# SDCard.net
KiCad netlist of a schematic drawn in Altium Designer
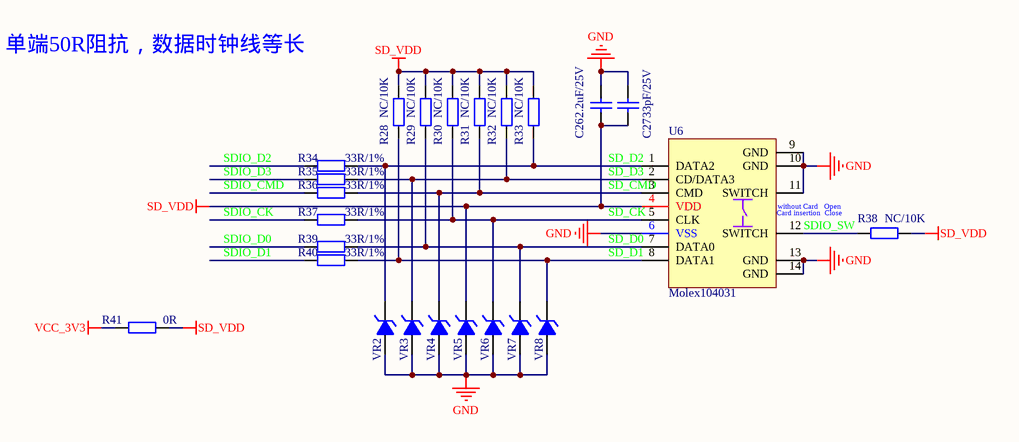
[diagram p0: SDCard.SchDoc]

(export (version "E")
  (design (tool "Eeschema 10.0.6"))
  (components
    (comp (ref "C26")
      (value "2.2uF/25V")
      (footprint "C0402_L")
      (description "贴片电容")
      (libsource (lib "0.1 - 电阻-电容-电感-晶振-晶体-磁珠-电位器") (part "C"))
    )
    (comp (ref "C27")
      (value "33pF/25V")
      (footprint "C0402_L")
      (description "贴片电容")
      (libsource (lib "0.1 - 电阻-电容-电感-晶振-晶体-磁珠-电位器") (part "C"))
    )
    (comp (ref "R28")
      (value "NC/10K")
      (footprint "R0402_L")
      (description "贴片电阻")
      (libsource (lib "0.1 - 电阻-电容-电感-晶振-晶体-磁珠-电位器") (part "R"))
    )
    (comp (ref "R29")
      (value "NC/10K")
      (footprint "R0402_L")
      (description "贴片电阻")
      (libsource (lib "0.1 - 电阻-电容-电感-晶振-晶体-磁珠-电位器") (part "R"))
    )
    (comp (ref "R30")
      (value "NC/10K")
      (footprint "R0402_L")
      (description "贴片电阻")
      (libsource (lib "0.1 - 电阻-电容-电感-晶振-晶体-磁珠-电位器") (part "R"))
    )
    (comp (ref "R31")
      (value "NC/10K")
      (footprint "R0402_L")
      (description "贴片电阻")
      (libsource (lib "0.1 - 电阻-电容-电感-晶振-晶体-磁珠-电位器") (part "R"))
    )
    (comp (ref "R32")
      (value "NC/10K")
      (footprint "R0402_L")
      (description "贴片电阻")
      (libsource (lib "0.1 - 电阻-电容-电感-晶振-晶体-磁珠-电位器") (part "R"))
    )
    (comp (ref "R33")
      (value "NC/10K")
      (footprint "R0402_L")
      (description "贴片电阻")
      (libsource (lib "0.1 - 电阻-电容-电感-晶振-晶体-磁珠-电位器") (part "R"))
    )
    (comp (ref "R34")
      (value "33R/1%")
      (footprint "R0402_L")
      (description "贴片电阻")
      (libsource (lib "0.1 - 电阻-电容-电感-晶振-晶体-磁珠-电位器") (part "R"))
    )
    (comp (ref "R35")
      (value "33R/1%")
      (footprint "R0402_L")
      (description "贴片电阻")
      (libsource (lib "0.1 - 电阻-电容-电感-晶振-晶体-磁珠-电位器") (part "R"))
    )
    (comp (ref "R36")
      (value "33R/1%")
      (footprint "R0402_L")
      (description "贴片电阻")
      (libsource (lib "0.1 - 电阻-电容-电感-晶振-晶体-磁珠-电位器") (part "R"))
    )
    (comp (ref "R37")
      (value "33R/1%")
      (footprint "R0402_L")
      (description "贴片电阻")
      (libsource (lib "0.1 - 电阻-电容-电感-晶振-晶体-磁珠-电位器") (part "R"))
    )
    (comp (ref "R38")
      (value "NC/10K")
      (footprint "R0402_L")
      (description "贴片电阻")
      (libsource (lib "0.1 - 电阻-电容-电感-晶振-晶体-磁珠-电位器") (part "R"))
    )
    (comp (ref "R39")
      (value "33R/1%")
      (footprint "R0402_L")
      (description "贴片电阻")
      (libsource (lib "0.1 - 电阻-电容-电感-晶振-晶体-磁珠-电位器") (part "R"))
    )
    (comp (ref "R40")
      (value "33R/1%")
      (footprint "R0402_L")
      (description "贴片电阻")
      (libsource (lib "0.1 - 电阻-电容-电感-晶振-晶体-磁珠-电位器") (part "R"))
    )
    (comp (ref "R41")
      (value "0R")
      (footprint "R0402_L")
      (description "贴片电阻")
      (libsource (lib "0.1 - 电阻-电容-电感-晶振-晶体-磁珠-电位器") (part "R"))
    )
    (comp (ref "U6")
      (value "Molex104031")
      (footprint "插拔式MicroSD卡")
      (description "拔插式超薄TF卡座")
      (libsource (lib "USER_Lib") (part "Molex104031"))
    )
    (comp (ref "VR2")
      (value "ESD9D5U")
      (footprint "SOD-923")
      (description "瞬态电压抑制二极管")
      (libsource (lib "二极管") (part "Diode4"))
    )
    (comp (ref "VR3")
      (value "ESD9D5U")
      (footprint "SOD-923")
      (description "瞬态电压抑制二极管")
      (libsource (lib "二极管") (part "Diode4"))
    )
    (comp (ref "VR4")
      (value "ESD9D5U")
      (footprint "SOD-923")
      (description "瞬态电压抑制二极管")
      (libsource (lib "二极管") (part "Diode4"))
    )
    (comp (ref "VR5")
      (value "ESD9D5U")
      (footprint "SOD-923")
      (description "瞬态电压抑制二极管")
      (libsource (lib "二极管") (part "Diode4"))
    )
    (comp (ref "VR6")
      (value "ESD9D5U")
      (footprint "SOD-923")
      (description "瞬态电压抑制二极管")
      (libsource (lib "二极管") (part "Diode4"))
    )
    (comp (ref "VR7")
      (value "ESD9D5U")
      (footprint "SOD-923")
      (description "瞬态电压抑制二极管")
      (libsource (lib "二极管") (part "Diode4"))
    )
    (comp (ref "VR8")
      (value "ESD9D5U")
      (footprint "SOD-923")
      (description "瞬态电压抑制二极管")
      (libsource (lib "二极管") (part "Diode4"))
    )
  )
  (nets
    (net (code "1") (name "/SDIO_CK") (class "Default")
      (node (ref "R37") (pin "1") (pinfunction "1_1") (pintype "passive"))
    )
    (net (code "2") (name "/SDIO_CMD") (class "Default")
      (node (ref "R36") (pin "1") (pinfunction "1_1") (pintype "passive"))
    )
    (net (code "3") (name "/SDIO_D0") (class "Default")
      (node (ref "R39") (pin "1") (pinfunction "1_1") (pintype "passive"))
    )
    (net (code "4") (name "/SDIO_D1") (class "Default")
      (node (ref "R40") (pin "1") (pinfunction "1_1") (pintype "passive"))
    )
    (net (code "5") (name "/SDIO_D2") (class "Default")
      (node (ref "R34") (pin "1") (pinfunction "1_1") (pintype "passive"))
    )
    (net (code "6") (name "/SDIO_D3") (class "Default")
      (node (ref "R35") (pin "1") (pinfunction "1_1") (pintype "passive"))
    )
    (net (code "7") (name "/SDIO_SW") (class "Default")
      (node (ref "R38") (pin "2") (pinfunction "2_2") (pintype "passive"))
      (node (ref "U6") (pin "12") (pinfunction "SWITCH_12") (pintype "passive"))
    )
    (net (code "8") (name "/SD_CK") (class "Default")
      (node (ref "R30") (pin "1") (pinfunction "1_1") (pintype "passive"))
      (node (ref "R37") (pin "2") (pinfunction "2_2") (pintype "passive"))
      (node (ref "U6") (pin "5") (pinfunction "CLK_5") (pintype "passive"))
      (node (ref "VR6") (pin "1") (pinfunction "K_1") (pintype "passive"))
    )
    (net (code "9") (name "/SD_CMD") (class "Default")
      (node (ref "R31") (pin "1") (pinfunction "1_1") (pintype "passive"))
      (node (ref "R36") (pin "2") (pinfunction "2_2") (pintype "passive"))
      (node (ref "U6") (pin "3") (pinfunction "CMD_3") (pintype "passive"))
      (node (ref "VR4") (pin "1") (pinfunction "K_1") (pintype "passive"))
    )
    (net (code "10") (name "/SD_D0") (class "Default")
      (node (ref "R29") (pin "1") (pinfunction "1_1") (pintype "passive"))
      (node (ref "R39") (pin "2") (pinfunction "2_2") (pintype "passive"))
      (node (ref "U6") (pin "7") (pinfunction "DATA0_7") (pintype "passive"))
      (node (ref "VR7") (pin "1") (pinfunction "K_1") (pintype "passive"))
    )
    (net (code "11") (name "/SD_D1") (class "Default")
      (node (ref "R28") (pin "1") (pinfunction "1_1") (pintype "passive"))
      (node (ref "R40") (pin "2") (pinfunction "2_2") (pintype "passive"))
      (node (ref "U6") (pin "8") (pinfunction "DATA1_8") (pintype "passive"))
      (node (ref "VR8") (pin "1") (pinfunction "K_1") (pintype "passive"))
    )
    (net (code "12") (name "/SD_D2") (class "Default")
      (node (ref "R33") (pin "1") (pinfunction "1_1") (pintype "passive"))
      (node (ref "R34") (pin "2") (pinfunction "2_2") (pintype "passive"))
      (node (ref "U6") (pin "1") (pinfunction "DATA2_1") (pintype "passive"))
      (node (ref "VR2") (pin "1") (pinfunction "K_1") (pintype "passive"))
    )
    (net (code "13") (name "/SD_D3") (class "Default")
      (node (ref "R32") (pin "1") (pinfunction "1_1") (pintype "passive"))
      (node (ref "R35") (pin "2") (pinfunction "2_2") (pintype "passive"))
      (node (ref "U6") (pin "2") (pinfunction "CD/DATA3_2") (pintype "passive"))
      (node (ref "VR3") (pin "1") (pinfunction "K_1") (pintype "passive"))
    )
    (net (code "14") (name "GND") (class "Default")
      (node (ref "C26") (pin "2") (pinfunction "2_2") (pintype "passive"))
      (node (ref "C27") (pin "2") (pinfunction "2_2") (pintype "passive"))
      (node (ref "U6") (pin "10") (pinfunction "GND_10") (pintype "passive"))
      (node (ref "U6") (pin "11") (pinfunction "SWITCH_11") (pintype "passive"))
      (node (ref "U6") (pin "13") (pinfunction "GND_13") (pintype "passive"))
      (node (ref "U6") (pin "14") (pinfunction "GND_14") (pintype "passive"))
      (node (ref "U6") (pin "6") (pinfunction "VSS_6") (pintype "passive"))
      (node (ref "U6") (pin "9") (pinfunction "GND_9") (pintype "passive"))
      (node (ref "VR2") (pin "2") (pinfunction "A_2") (pintype "passive"))
      (node (ref "VR3") (pin "2") (pinfunction "A_2") (pintype "passive"))
      (node (ref "VR4") (pin "2") (pinfunction "A_2") (pintype "passive"))
      (node (ref "VR5") (pin "2") (pinfunction "A_2") (pintype "passive"))
      (node (ref "VR6") (pin "2") (pinfunction "A_2") (pintype "passive"))
      (node (ref "VR7") (pin "2") (pinfunction "A_2") (pintype "passive"))
      (node (ref "VR8") (pin "2") (pinfunction "A_2") (pintype "passive"))
    )
    (net (code "15") (name "SD_VDD") (class "Default")
      (node (ref "C26") (pin "1") (pinfunction "1_1") (pintype "passive"))
      (node (ref "C27") (pin "1") (pinfunction "1_1") (pintype "passive"))
      (node (ref "R28") (pin "2") (pinfunction "2_2") (pintype "passive"))
      (node (ref "R29") (pin "2") (pinfunction "2_2") (pintype "passive"))
      (node (ref "R30") (pin "2") (pinfunction "2_2") (pintype "passive"))
      (node (ref "R31") (pin "2") (pinfunction "2_2") (pintype "passive"))
      (node (ref "R32") (pin "2") (pinfunction "2_2") (pintype "passive"))
      (node (ref "R33") (pin "2") (pinfunction "2_2") (pintype "passive"))
      (node (ref "R38") (pin "1") (pinfunction "1_1") (pintype "passive"))
      (node (ref "R41") (pin "2") (pinfunction "2_2") (pintype "passive"))
      (node (ref "U6") (pin "4") (pinfunction "VDD_4") (pintype "passive"))
      (node (ref "VR5") (pin "1") (pinfunction "K_1") (pintype "passive"))
    )
    (net (code "16") (name "VCC_3V3") (class "Default")
      (node (ref "R41") (pin "1") (pinfunction "1_1") (pintype "passive"))
    )
  )
)
